# PLL_Counter_plain.net
KiCad netlist of a schematic drawn in EAGLE
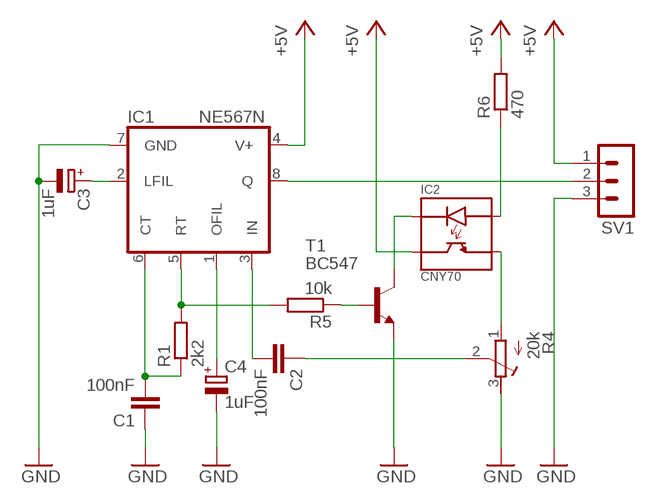
[diagram p0: schematic, sheet 1]

(export (version "E")
  (design (tool "Eeschema 10.0.6"))
  (components
    (comp (ref "C1")
      (value "100nF")
      (footprint "eagle-import:C025-025X050")
      (libsource (lib "eagle-import") (part "C-EU025-025X050"))
    )
    (comp (ref "C2")
      (value "100nF")
      (footprint "eagle-import:C025-025X050")
      (libsource (lib "eagle-import") (part "C-EU025-025X050"))
    )
    (comp (ref "C3")
      (value "1uF")
      (footprint "eagle-import:E2,5-5")
      (libsource (lib "eagle-import") (part "CPOL-EUE2.5-5"))
    )
    (comp (ref "C4")
      (value "1uF")
      (footprint "eagle-import:E2,5-5")
      (libsource (lib "eagle-import") (part "CPOL-EUE2.5-5"))
    )
    (comp (ref "IC1")
      (value "NE567N")
      (footprint "eagle-import:DIL08")
      (libsource (lib "eagle-import") (part "567NNE"))
    )
    (comp (ref "IC2")
      (value "CNY70")
      (footprint "eagle-import:CNY70")
      (libsource (lib "eagle-import") (part "CNY70"))
    )
    (comp (ref "R1")
      (value "2k2")
      (footprint "eagle-import:0204_7")
      (libsource (lib "eagle-import") (part "R-EU_0204/7"))
    )
    (comp (ref "R4")
      (value "20k")
      (footprint "eagle-import:RTRIM64X")
      (libsource (lib "eagle-import") (part "R-TRIMM64X"))
    )
    (comp (ref "R5")
      (value "10k")
      (footprint "eagle-import:0204_7")
      (libsource (lib "eagle-import") (part "R-EU_0204/7"))
    )
    (comp (ref "R6")
      (value "470")
      (footprint "eagle-import:0204_7")
      (libsource (lib "eagle-import") (part "R-EU_0204/7"))
    )
    (comp (ref "SV1")
      (value "MA03-1")
      (footprint "eagle-import:MA03-1")
      (libsource (lib "eagle-import") (part "MA03-1"))
    )
    (comp (ref "T1")
      (value "BC547")
      (footprint "eagle-import:TO92")
      (libsource (lib "eagle-import") (part "BC547"))
    )
  )
  (nets
    (net (code "1") (name "+5V") (class "Default")
      (node (ref "IC1") (pin "4") (pinfunction "V+_4") (pintype "power_in"))
      (node (ref "IC2") (pin "DC") (pinfunction "DC_DC") (pintype "bidirectional"))
      (node (ref "R6") (pin "2") (pinfunction "2_2") (pintype "passive"))
      (node (ref "SV1") (pin "1") (pinfunction "1_1") (pintype "passive"))
    )
    (net (code "2") (name "GND") (class "Default")
      (node (ref "C1") (pin "1") (pinfunction "1_1") (pintype "passive"))
      (node (ref "C3") (pin "-") (pinfunction "-_-") (pintype "passive"))
      (node (ref "C4") (pin "-") (pinfunction "-_-") (pintype "passive"))
      (node (ref "IC1") (pin "7") (pinfunction "GND_7") (pintype "power_in"))
      (node (ref "R4") (pin "3") (pinfunction "E_3") (pintype "passive"))
      (node (ref "SV1") (pin "3") (pinfunction "3_3") (pintype "passive"))
      (node (ref "T1") (pin "1") (pinfunction "E_1") (pintype "passive"))
    )
    (net (code "3") (name "Net-(IC1-CT)") (class "Default")
      (node (ref "C1") (pin "2") (pinfunction "2_2") (pintype "passive"))
      (node (ref "IC1") (pin "6") (pinfunction "CT_6") (pintype "passive"))
      (node (ref "R1") (pin "1") (pinfunction "1_1") (pintype "passive"))
    )
    (net (code "4") (name "Net-(IC1-IN)") (class "Default")
      (node (ref "C2") (pin "2") (pinfunction "2_2") (pintype "passive"))
      (node (ref "IC1") (pin "3") (pinfunction "IN_3") (pintype "input"))
    )
    (net (code "5") (name "Net-(IC1-LFIL)") (class "Default")
      (node (ref "C3") (pin "+") (pinfunction "+_+") (pintype "passive"))
      (node (ref "IC1") (pin "2") (pinfunction "LFIL_2") (pintype "passive"))
    )
    (net (code "6") (name "Net-(IC1-OFIL)") (class "Default")
      (node (ref "C4") (pin "+") (pinfunction "+_+") (pintype "passive"))
      (node (ref "IC1") (pin "1") (pinfunction "OFIL_1") (pintype "output"))
    )
    (net (code "7") (name "Net-(IC1-Q)") (class "Default")
      (node (ref "IC1") (pin "8") (pinfunction "Q_8") (pintype "output"))
      (node (ref "SV1") (pin "2") (pinfunction "2_2") (pintype "passive"))
    )
    (net (code "8") (name "Net-(IC1-RT)") (class "Default")
      (node (ref "IC1") (pin "5") (pinfunction "RT_5") (pintype "passive"))
      (node (ref "R1") (pin "2") (pinfunction "2_2") (pintype "passive"))
      (node (ref "R5") (pin "2") (pinfunction "2_2") (pintype "passive"))
    )
    (net (code "9") (name "Net-(IC2-PadEA)") (class "Default")
      (node (ref "IC2") (pin "EA") (pinfunction "EA_EA") (pintype "bidirectional"))
      (node (ref "R6") (pin "1") (pinfunction "1_1") (pintype "passive"))
    )
    (net (code "10") (name "Net-(R4-A)") (class "Default")
      (node (ref "IC2") (pin "DE") (pinfunction "DE_DE") (pintype "bidirectional"))
      (node (ref "R4") (pin "1") (pinfunction "A_1") (pintype "passive"))
    )
    (net (code "11") (name "Net-(R4-S)") (class "Default")
      (node (ref "C2") (pin "1") (pinfunction "1_1") (pintype "passive"))
      (node (ref "R4") (pin "2") (pinfunction "S_2") (pintype "passive"))
    )
    (net (code "12") (name "Net-(T1-B)") (class "Default")
      (node (ref "R5") (pin "1") (pinfunction "1_1") (pintype "passive"))
      (node (ref "T1") (pin "2") (pinfunction "B_2") (pintype "passive"))
    )
    (net (code "13") (name "Net-(T1-C)") (class "Default")
      (node (ref "IC2") (pin "EK") (pinfunction "EK_EK") (pintype "bidirectional"))
      (node (ref "T1") (pin "3") (pinfunction "C_3") (pintype "passive"))
    )
  )
)
